# owl-digital.net
KiCad netlist of a schematic drawn in EAGLE
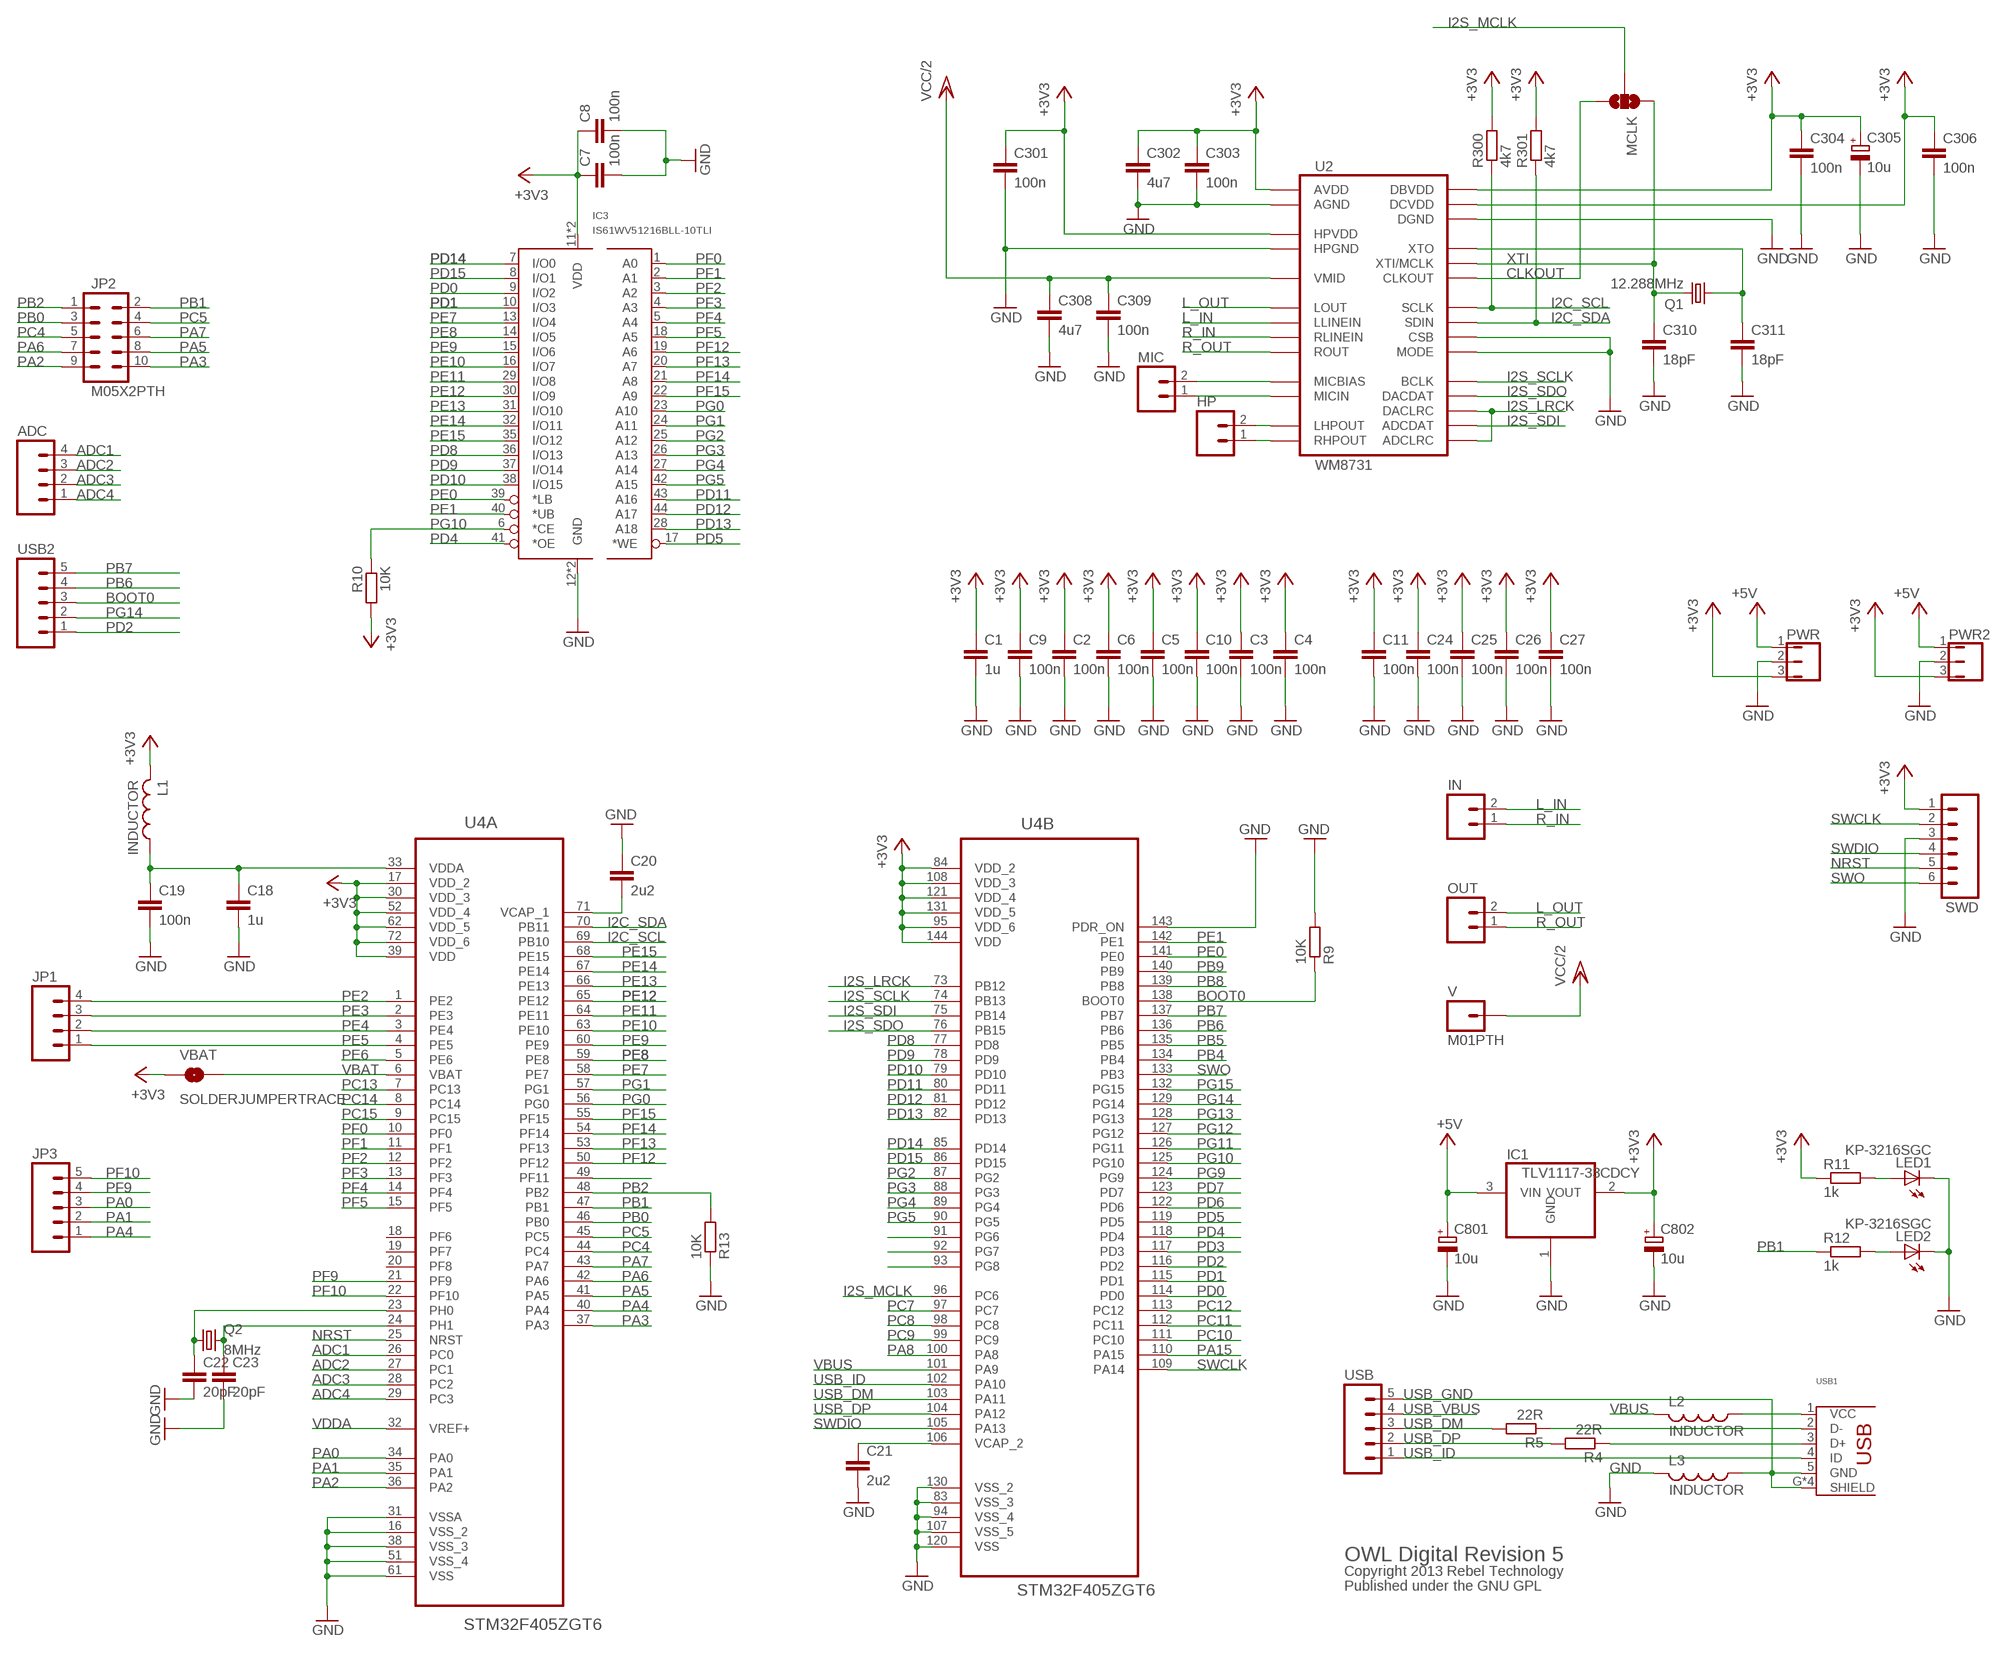
[diagram p0: schematic, sheet 1]

(export (version "E")
  (design (tool "Eeschema 10.0.6"))
  (components
    (comp (ref "ADC")
      (value "M04PTH")
      (footprint "eagle-import:1X04")
      (libsource (lib "eagle-import") (part "M04PTH"))
    )
    (comp (ref "C1")
      (value "1u")
      (footprint "eagle-import:C0603")
      (libsource (lib "eagle-import") (part "C-EUC0603"))
    )
    (comp (ref "C2")
      (value "100n")
      (footprint "eagle-import:C0603")
      (libsource (lib "eagle-import") (part "C-EUC0603"))
    )
    (comp (ref "C3")
      (value "100n")
      (footprint "eagle-import:C0603")
      (libsource (lib "eagle-import") (part "C-EUC0603"))
    )
    (comp (ref "C4")
      (value "100n")
      (footprint "eagle-import:C0603")
      (libsource (lib "eagle-import") (part "C-EUC0603"))
    )
    (comp (ref "C5")
      (value "100n")
      (footprint "eagle-import:C0603")
      (libsource (lib "eagle-import") (part "C-EUC0603"))
    )
    (comp (ref "C6")
      (value "100n")
      (footprint "eagle-import:C0603")
      (libsource (lib "eagle-import") (part "C-EUC0603"))
    )
    (comp (ref "C7")
      (value "100n")
      (footprint "eagle-import:C0603")
      (libsource (lib "eagle-import") (part "C-EUC0603"))
    )
    (comp (ref "C8")
      (value "100n")
      (footprint "eagle-import:C0603")
      (libsource (lib "eagle-import") (part "C-EUC0603"))
    )
    (comp (ref "C9")
      (value "100n")
      (footprint "eagle-import:C0603")
      (libsource (lib "eagle-import") (part "C-EUC0603"))
    )
    (comp (ref "C10")
      (value "100n")
      (footprint "eagle-import:C0603")
      (libsource (lib "eagle-import") (part "C-EUC0603"))
    )
    (comp (ref "C11")
      (value "100n")
      (footprint "eagle-import:C0603")
      (libsource (lib "eagle-import") (part "C-EUC0603"))
    )
    (comp (ref "C18")
      (value "1u")
      (footprint "eagle-import:C0603")
      (libsource (lib "eagle-import") (part "C-EUC0603"))
    )
    (comp (ref "C19")
      (value "100n")
      (footprint "eagle-import:C0603")
      (libsource (lib "eagle-import") (part "C-EUC0603"))
    )
    (comp (ref "C20")
      (value "2u2")
      (footprint "eagle-import:C0603")
      (libsource (lib "eagle-import") (part "C-EUC0603"))
    )
    (comp (ref "C21")
      (value "2u2")
      (footprint "eagle-import:C0603")
      (libsource (lib "eagle-import") (part "C-EUC0603"))
    )
    (comp (ref "C22")
      (value "20pF")
      (footprint "eagle-import:C0603")
      (libsource (lib "eagle-import") (part "C-EUC0603"))
    )
    (comp (ref "C23")
      (value "20pF")
      (footprint "eagle-import:C0603")
      (libsource (lib "eagle-import") (part "C-EUC0603"))
    )
    (comp (ref "C24")
      (value "100n")
      (footprint "eagle-import:C0603")
      (libsource (lib "eagle-import") (part "C-EUC0603"))
    )
    (comp (ref "C25")
      (value "100n")
      (footprint "eagle-import:C0603")
      (libsource (lib "eagle-import") (part "C-EUC0603"))
    )
    (comp (ref "C26")
      (value "100n")
      (footprint "eagle-import:C0603")
      (libsource (lib "eagle-import") (part "C-EUC0603"))
    )
    (comp (ref "C27")
      (value "100n")
      (footprint "eagle-import:C0603")
      (libsource (lib "eagle-import") (part "C-EUC0603"))
    )
    (comp (ref "C301")
      (value "100n")
      (footprint "eagle-import:C0603")
      (libsource (lib "eagle-import") (part "C-EUC0603"))
    )
    (comp (ref "C302")
      (value "4u7")
      (footprint "eagle-import:C1206")
      (libsource (lib "eagle-import") (part "C-EUC1206"))
    )
    (comp (ref "C303")
      (value "100n")
      (footprint "eagle-import:C0603")
      (libsource (lib "eagle-import") (part "C-EUC0603"))
    )
    (comp (ref "C304")
      (value "100n")
      (footprint "eagle-import:C0603")
      (libsource (lib "eagle-import") (part "C-EUC0603"))
    )
    (comp (ref "C305")
      (value "10u")
      (footprint "eagle-import:PANASONIC_A")
      (libsource (lib "eagle-import") (part "CPOL-EUA"))
    )
    (comp (ref "C306")
      (value "100n")
      (footprint "eagle-import:C0603")
      (libsource (lib "eagle-import") (part "C-EUC0603"))
    )
    (comp (ref "C308")
      (value "4u7")
      (footprint "eagle-import:C1206")
      (libsource (lib "eagle-import") (part "C-EUC1206"))
    )
    (comp (ref "C309")
      (value "100n")
      (footprint "eagle-import:C0603")
      (libsource (lib "eagle-import") (part "C-EUC0603"))
    )
    (comp (ref "C310")
      (value "18pF")
      (footprint "eagle-import:C0603")
      (libsource (lib "eagle-import") (part "C-EUC0603"))
    )
    (comp (ref "C311")
      (value "18pF")
      (footprint "eagle-import:C0603")
      (libsource (lib "eagle-import") (part "C-EUC0603"))
    )
    (comp (ref "C801")
      (value "10u")
      (footprint "eagle-import:PANASONIC_A")
      (libsource (lib "eagle-import") (part "CPOL-EUA"))
    )
    (comp (ref "C802")
      (value "10u")
      (footprint "eagle-import:PANASONIC_A")
      (libsource (lib "eagle-import") (part "CPOL-EUA"))
    )
    (comp (ref "HP")
      (value "M02PTH")
      (footprint "eagle-import:1X02")
      (libsource (lib "eagle-import") (part "M02PTH"))
    )
    (comp (ref "IC1")
      (value "TLV1117-33CDCY")
      (footprint "eagle-import:SOT223")
      (fields (field (name "MPN") "REG1117"))
      (libsource (lib "eagle-import") (part "REG1117"))
    )
    (comp (ref "IC3")
      (value "IS61WV51216BLL-10TLI")
      (footprint "eagle-import:TSOP44-II")
      (libsource (lib "eagle-import") (part "IS61WV51216BLL-10TLI"))
    )
    (comp (ref "IN")
      (value "M02PTH")
      (footprint "eagle-import:1X02")
      (libsource (lib "eagle-import") (part "M02PTH"))
    )
    (comp (ref "JP1")
      (value "M04PTH")
      (footprint "eagle-import:1X04")
      (libsource (lib "eagle-import") (part "M04PTH"))
    )
    (comp (ref "JP2")
      (value "M05X2PTH")
      (footprint "eagle-import:AVR_ICSP")
      (libsource (lib "eagle-import") (part "M05X2PTH"))
    )
    (comp (ref "JP3")
      (value "M05PTH")
      (footprint "eagle-import:1X05")
      (libsource (lib "eagle-import") (part "M05PTH"))
    )
    (comp (ref "L1")
      (value "INDUCTOR")
      (footprint "eagle-import:0603")
      (libsource (lib "eagle-import") (part "INDUCTOR"))
    )
    (comp (ref "L2")
      (value "INDUCTOR")
      (footprint "eagle-import:0603")
      (libsource (lib "eagle-import") (part "INDUCTOR"))
    )
    (comp (ref "L3")
      (value "INDUCTOR")
      (footprint "eagle-import:0603")
      (libsource (lib "eagle-import") (part "INDUCTOR"))
    )
    (comp (ref "LED1")
      (value "KP-3216SGC")
      (footprint "eagle-import:LED-1206")
      (libsource (lib "eagle-import") (part "LED1206"))
    )
    (comp (ref "LED2")
      (value "KP-3216SGC")
      (footprint "eagle-import:LED-1206")
      (libsource (lib "eagle-import") (part "LED1206"))
    )
    (comp (ref "MCLK")
      (value "SOLDERJUMPER_2WAY")
      (footprint "eagle-import:SJ_3_SML")
      (libsource (lib "eagle-import") (part "SOLDERJUMPER_2WAY"))
    )
    (comp (ref "MIC")
      (value "M02PTH")
      (footprint "eagle-import:1X02")
      (libsource (lib "eagle-import") (part "M02PTH"))
    )
    (comp (ref "OUT")
      (value "M02PTH")
      (footprint "eagle-import:1X02")
      (libsource (lib "eagle-import") (part "M02PTH"))
    )
    (comp (ref "PWR")
      (value "JMP/3P/SIP")
      (footprint "eagle-import:JMP_3P_SIP")
      (libsource (lib "eagle-import") (part "JMP/3P/SIP"))
    )
    (comp (ref "PWR2")
      (value "JMP/3P/SIP")
      (footprint "eagle-import:JMP_3P_SIP")
      (libsource (lib "eagle-import") (part "JMP/3P/SIP"))
    )
    (comp (ref "Q1")
      (value "12.288MHz")
      (footprint "eagle-import:HC49UP")
      (libsource (lib "eagle-import") (part "CRYSTALHC49UP"))
    )
    (comp (ref "Q2")
      (value "8MHz")
      (footprint "eagle-import:HC49UP")
      (libsource (lib "eagle-import") (part "CRYSTALHC49UP"))
    )
    (comp (ref "R4")
      (value "22R")
      (footprint "eagle-import:0603")
      (libsource (lib "eagle-import") (part "R-EU_0603"))
    )
    (comp (ref "R5")
      (value "22R")
      (footprint "eagle-import:0603")
      (libsource (lib "eagle-import") (part "R-EU_0603"))
    )
    (comp (ref "R9")
      (value "10K")
      (footprint "eagle-import:0603")
      (libsource (lib "eagle-import") (part "R-EU_0603"))
    )
    (comp (ref "R10")
      (value "10K")
      (footprint "eagle-import:0603")
      (libsource (lib "eagle-import") (part "R-EU_0603"))
    )
    (comp (ref "R11")
      (value "1k")
      (footprint "eagle-import:0603")
      (libsource (lib "eagle-import") (part "R-EU_0603"))
    )
    (comp (ref "R12")
      (value "1k")
      (footprint "eagle-import:0603")
      (libsource (lib "eagle-import") (part "R-EU_0603"))
    )
    (comp (ref "R13")
      (value "10K")
      (footprint "eagle-import:0603")
      (libsource (lib "eagle-import") (part "R-EU_0603"))
    )
    (comp (ref "R300")
      (value "4k7")
      (footprint "eagle-import:0603")
      (libsource (lib "eagle-import") (part "R-EU_0603"))
    )
    (comp (ref "R301")
      (value "4k7")
      (footprint "eagle-import:0603")
      (libsource (lib "eagle-import") (part "R-EU_0603"))
    )
    (comp (ref "SWD")
      (value "M06SIP")
      (footprint "eagle-import:1X06")
      (libsource (lib "eagle-import") (part "M06SIP"))
    )
    (comp (ref "U2")
      (value "WM8731")
      (footprint "eagle-import:28-SSOP")
      (libsource (lib "eagle-import") (part "WM8731"))
    )
    (comp (ref "U4")
      (value "STM32F405ZGT6")
      (footprint "eagle-import:QFP50P2200X2200X160-144N")
      (fields (field (name "FARNELL") "221-5225"))
      (libsource (lib "eagle-import") (part "STM32F405ZGT6"))
    )
    (comp (ref "USB")
      (value "M05PTH")
      (footprint "eagle-import:1X05")
      (libsource (lib "eagle-import") (part "M05PTH"))
    )
    (comp (ref "USB1")
      (value "USB_HRS_ZX62-B-5PA(11)MICRO.B")
      (footprint "eagle-import:HRS_ZX62RD-AB-5P8")
      (libsource (lib "eagle-import") (part "USB_HRS_ZX62-B-5PA(11)MICRO.B"))
    )
    (comp (ref "USB2")
      (value "M05PTH")
      (footprint "eagle-import:1X05")
      (libsource (lib "eagle-import") (part "M05PTH"))
    )
    (comp (ref "V")
      (value "M01PTH")
      (footprint "eagle-import:1X01")
      (libsource (lib "eagle-import") (part "M01PTH"))
    )
    (comp (ref "VBAT")
      (value "SOLDERJUMPERTRACE")
      (footprint "eagle-import:SJ_2S-TRACE")
      (libsource (lib "eagle-import") (part "SOLDERJUMPERTRACE"))
    )
  )
  (nets
    (net (code "1") (name "+3V3") (class "Default")
      (node (ref "C1") (pin "1") (pinfunction "1_1") (pintype "passive"))
      (node (ref "C10") (pin "1") (pinfunction "1_1") (pintype "passive"))
      (node (ref "C11") (pin "1") (pinfunction "1_1") (pintype "passive"))
      (node (ref "C2") (pin "1") (pinfunction "1_1") (pintype "passive"))
      (node (ref "C24") (pin "1") (pinfunction "1_1") (pintype "passive"))
      (node (ref "C25") (pin "1") (pinfunction "1_1") (pintype "passive"))
      (node (ref "C26") (pin "1") (pinfunction "1_1") (pintype "passive"))
      (node (ref "C27") (pin "1") (pinfunction "1_1") (pintype "passive"))
      (node (ref "C3") (pin "1") (pinfunction "1_1") (pintype "passive"))
      (node (ref "C301") (pin "1") (pinfunction "1_1") (pintype "passive"))
      (node (ref "C302") (pin "1") (pinfunction "1_1") (pintype "passive"))
      (node (ref "C303") (pin "1") (pinfunction "1_1") (pintype "passive"))
      (node (ref "C304") (pin "1") (pinfunction "1_1") (pintype "passive"))
      (node (ref "C305") (pin "+") (pinfunction "+_+") (pintype "passive"))
      (node (ref "C306") (pin "1") (pinfunction "1_1") (pintype "passive"))
      (node (ref "C4") (pin "1") (pinfunction "1_1") (pintype "passive"))
      (node (ref "C5") (pin "1") (pinfunction "1_1") (pintype "passive"))
      (node (ref "C6") (pin "1") (pinfunction "1_1") (pintype "passive"))
      (node (ref "C7") (pin "1") (pinfunction "1_1") (pintype "passive"))
      (node (ref "C8") (pin "1") (pinfunction "1_1") (pintype "passive"))
      (node (ref "C802") (pin "+") (pinfunction "+_+") (pintype "passive"))
      (node (ref "C9") (pin "1") (pinfunction "1_1") (pintype "passive"))
      (node (ref "IC1") (pin "2") (pinfunction "VOUT_2") (pintype "output"))
      (node (ref "IC3") (pin "11") (pinfunction "VDD_11") (pintype "power_in"))
      (node (ref "IC3") (pin "33") (pinfunction "VDD_33") (pintype "power_in"))
      (node (ref "L1") (pin "2") (pinfunction "2_2") (pintype "passive"))
      (node (ref "PWR") (pin "3") (pinfunction "3_3") (pintype "passive"))
      (node (ref "PWR2") (pin "3") (pinfunction "3_3") (pintype "passive"))
      (node (ref "R10") (pin "2") (pinfunction "2_2") (pintype "passive"))
      (node (ref "R11") (pin "1") (pinfunction "1_1") (pintype "passive"))
      (node (ref "R300") (pin "2") (pinfunction "2_2") (pintype "passive"))
      (node (ref "R301") (pin "2") (pinfunction "2_2") (pintype "passive"))
      (node (ref "SWD") (pin "1") (pinfunction "1_1") (pintype "passive"))
      (node (ref "U2") (pin "P$1") (pinfunction "DBVDD_P$1") (pintype "power_in"))
      (node (ref "U2") (pin "P$14") (pinfunction "AVDD_P$14") (pintype "power_in"))
      (node (ref "U2") (pin "P$27") (pinfunction "DCVDD_P$27") (pintype "power_in"))
      (node (ref "U2") (pin "P$8") (pinfunction "HPVDD_P$8") (pintype "power_in"))
      (node (ref "U4") (pin "108") (pinfunction "VDD_3_108") (pintype "power_in"))
      (node (ref "U4") (pin "121") (pinfunction "VDD_4_121") (pintype "power_in"))
      (node (ref "U4") (pin "131") (pinfunction "VDD_5_131") (pintype "power_in"))
      (node (ref "U4") (pin "144") (pinfunction "VDD_144") (pintype "power_in"))
      (node (ref "U4") (pin "17") (pinfunction "VDD_2_17") (pintype "power_in"))
      (node (ref "U4") (pin "30") (pinfunction "VDD_3_30") (pintype "power_in"))
      (node (ref "U4") (pin "39") (pinfunction "VDD_39") (pintype "power_in"))
      (node (ref "U4") (pin "52") (pinfunction "VDD_4_52") (pintype "power_in"))
      (node (ref "U4") (pin "62") (pinfunction "VDD_5_62") (pintype "power_in"))
      (node (ref "U4") (pin "72") (pinfunction "VDD_6_72") (pintype "power_in"))
      (node (ref "U4") (pin "84") (pinfunction "VDD_2_84") (pintype "power_in"))
      (node (ref "U4") (pin "95") (pinfunction "VDD_6_95") (pintype "power_in"))
      (node (ref "VBAT") (pin "1") (pinfunction "1_1") (pintype "passive"))
    )
    (net (code "2") (name "+5V") (class "Default")
      (node (ref "C801") (pin "+") (pinfunction "+_+") (pintype "passive"))
      (node (ref "IC1") (pin "3") (pinfunction "VIN_3") (pintype "input"))
      (node (ref "PWR") (pin "1") (pinfunction "1_1") (pintype "passive"))
      (node (ref "PWR2") (pin "1") (pinfunction "1_1") (pintype "passive"))
    )
    (net (code "3") (name "/ADC1") (class "Default")
      (node (ref "ADC") (pin "4") (pinfunction "4_4") (pintype "passive"))
      (node (ref "U4") (pin "26") (pinfunction "PC0_26") (pintype "bidirectional"))
    )
    (net (code "4") (name "/ADC2") (class "Default")
      (node (ref "ADC") (pin "3") (pinfunction "3_3") (pintype "passive"))
      (node (ref "U4") (pin "27") (pinfunction "PC1_27") (pintype "bidirectional"))
    )
    (net (code "5") (name "/ADC3") (class "Default")
      (node (ref "ADC") (pin "2") (pinfunction "2_2") (pintype "passive"))
      (node (ref "U4") (pin "28") (pinfunction "PC2_28") (pintype "bidirectional"))
    )
    (net (code "6") (name "/ADC4") (class "Default")
      (node (ref "ADC") (pin "1") (pinfunction "1_1") (pintype "passive"))
      (node (ref "U4") (pin "29") (pinfunction "PC3_29") (pintype "bidirectional"))
    )
    (net (code "7") (name "/BOOT0") (class "Default")
      (node (ref "R9") (pin "1") (pinfunction "1_1") (pintype "passive"))
      (node (ref "U4") (pin "138") (pinfunction "BOOT0_138") (pintype "passive"))
      (node (ref "USB2") (pin "3") (pinfunction "3_3") (pintype "passive"))
    )
    (net (code "8") (name "/CLKOUT") (class "Default")
      (node (ref "MCLK") (pin "3") (pinfunction "3_3") (pintype "passive"))
      (node (ref "U2") (pin "P$2") (pinfunction "CLKOUT_P$2") (pintype "output"))
    )
    (net (code "9") (name "/I2C_SCL") (class "Default")
      (node (ref "R300") (pin "1") (pinfunction "1_1") (pintype "passive"))
      (node (ref "U2") (pin "P$24") (pinfunction "SCLK_P$24") (pintype "input"))
      (node (ref "U4") (pin "69") (pinfunction "PB10_69") (pintype "bidirectional"))
    )
    (net (code "10") (name "/I2C_SDA") (class "Default")
      (node (ref "R301") (pin "1") (pinfunction "1_1") (pintype "passive"))
      (node (ref "U2") (pin "P$23") (pinfunction "SDIN_P$23") (pintype "bidirectional"))
      (node (ref "U4") (pin "70") (pinfunction "PB11_70") (pintype "bidirectional"))
    )
    (net (code "11") (name "/I2S_LRCK") (class "Default")
      (node (ref "U2") (pin "P$5") (pinfunction "DACLRC_P$5") (pintype "bidirectional"))
      (node (ref "U2") (pin "P$7") (pinfunction "ADCLRC_P$7") (pintype "bidirectional"))
      (node (ref "U4") (pin "73") (pinfunction "PB12_73") (pintype "bidirectional"))
    )
    (net (code "12") (name "/I2S_MCLK") (class "Default")
      (node (ref "MCLK") (pin "2") (pinfunction "2_2") (pintype "passive"))
      (node (ref "U4") (pin "96") (pinfunction "PC6_96") (pintype "bidirectional"))
    )
    (net (code "13") (name "/I2S_SCLK") (class "Default")
      (node (ref "U2") (pin "P$3") (pinfunction "BCLK_P$3") (pintype "bidirectional"))
      (node (ref "U4") (pin "74") (pinfunction "PB13_74") (pintype "bidirectional"))
    )
    (net (code "14") (name "/I2S_SDI") (class "Default")
      (node (ref "U2") (pin "P$6") (pinfunction "ADCDAT_P$6") (pintype "output"))
      (node (ref "U4") (pin "75") (pinfunction "PB14_75") (pintype "bidirectional"))
    )
    (net (code "15") (name "/I2S_SDO") (class "Default")
      (node (ref "U2") (pin "P$4") (pinfunction "DACDAT_P$4") (pintype "input"))
      (node (ref "U4") (pin "76") (pinfunction "PB15_76") (pintype "bidirectional"))
    )
    (net (code "16") (name "/L_IN") (class "Default")
      (node (ref "IN") (pin "2") (pinfunction "2_2") (pintype "passive"))
      (node (ref "U2") (pin "P$20") (pinfunction "LLINEIN_P$20") (pintype "input"))
    )
    (net (code "17") (name "/L_OUT") (class "Default")
      (node (ref "OUT") (pin "2") (pinfunction "2_2") (pintype "passive"))
      (node (ref "U2") (pin "P$12") (pinfunction "LOUT_P$12") (pintype "output"))
    )
    (net (code "18") (name "/NRST") (class "Default")
      (node (ref "SWD") (pin "5") (pinfunction "5_5") (pintype "passive"))
      (node (ref "U4") (pin "25") (pinfunction "NRST_25") (pintype "passive"))
    )
    (net (code "19") (name "/PA0") (class "Default")
      (node (ref "JP3") (pin "3") (pinfunction "3_3") (pintype "passive"))
      (node (ref "U4") (pin "34") (pinfunction "PA0_34") (pintype "bidirectional"))
    )
    (net (code "20") (name "/PA1") (class "Default")
      (node (ref "JP3") (pin "2") (pinfunction "2_2") (pintype "passive"))
      (node (ref "U4") (pin "35") (pinfunction "PA1_35") (pintype "bidirectional"))
    )
    (net (code "21") (name "/PA2") (class "Default")
      (node (ref "JP2") (pin "9") (pinfunction "9_9") (pintype "passive"))
      (node (ref "U4") (pin "36") (pinfunction "PA2_36") (pintype "bidirectional"))
    )
    (net (code "22") (name "/PA3") (class "Default")
      (node (ref "JP2") (pin "10") (pinfunction "10_10") (pintype "passive"))
      (node (ref "U4") (pin "37") (pinfunction "PA3_37") (pintype "bidirectional"))
    )
    (net (code "23") (name "/PA4") (class "Default")
      (node (ref "JP3") (pin "1") (pinfunction "1_1") (pintype "passive"))
      (node (ref "U4") (pin "40") (pinfunction "PA4_40") (pintype "bidirectional"))
    )
    (net (code "24") (name "/PA5") (class "Default")
      (node (ref "JP2") (pin "8") (pinfunction "8_8") (pintype "passive"))
      (node (ref "U4") (pin "41") (pinfunction "PA5_41") (pintype "bidirectional"))
    )
    (net (code "25") (name "/PA6") (class "Default")
      (node (ref "JP2") (pin "7") (pinfunction "7_7") (pintype "passive"))
      (node (ref "U4") (pin "42") (pinfunction "PA6_42") (pintype "bidirectional"))
    )
    (net (code "26") (name "/PA7") (class "Default")
      (node (ref "JP2") (pin "6") (pinfunction "6_6") (pintype "passive"))
      (node (ref "U4") (pin "43") (pinfunction "PA7_43") (pintype "bidirectional"))
    )
    (net (code "27") (name "/PA8") (class "Default")
      (node (ref "U4") (pin "100") (pinfunction "PA8_100") (pintype "bidirectional"))
    )
    (net (code "28") (name "/PA15") (class "Default")
      (node (ref "U4") (pin "110") (pinfunction "PA15_110") (pintype "bidirectional"))
    )
    (net (code "29") (name "/PB0") (class "Default")
      (node (ref "JP2") (pin "3") (pinfunction "3_3") (pintype "passive"))
      (node (ref "U4") (pin "46") (pinfunction "PB0_46") (pintype "bidirectional"))
    )
    (net (code "30") (name "/PB1") (class "Default")
      (node (ref "JP2") (pin "2") (pinfunction "2_2") (pintype "passive"))
      (node (ref "R12") (pin "1") (pinfunction "1_1") (pintype "passive"))
      (node (ref "U4") (pin "47") (pinfunction "PB1_47") (pintype "bidirectional"))
    )
    (net (code "31") (name "/PB2") (class "Default")
      (node (ref "JP2") (pin "1") (pinfunction "1_1") (pintype "passive"))
      (node (ref "R13") (pin "2") (pinfunction "2_2") (pintype "passive"))
      (node (ref "U4") (pin "48") (pinfunction "PB2_48") (pintype "bidirectional"))
    )
    (net (code "32") (name "/PB4") (class "Default")
      (node (ref "U4") (pin "134") (pinfunction "PB4_134") (pintype "bidirectional"))
    )
    (net (code "33") (name "/PB5") (class "Default")
      (node (ref "U4") (pin "135") (pinfunction "PB5_135") (pintype "bidirectional"))
    )
    (net (code "34") (name "/PB6") (class "Default")
      (node (ref "U4") (pin "136") (pinfunction "PB6_136") (pintype "bidirectional"))
      (node (ref "USB2") (pin "4") (pinfunction "4_4") (pintype "passive"))
    )
    (net (code "35") (name "/PB7") (class "Default")
      (node (ref "U4") (pin "137") (pinfunction "PB7_137") (pintype "bidirectional"))
      (node (ref "USB2") (pin "5") (pinfunction "5_5") (pintype "passive"))
    )
    (net (code "36") (name "/PB8") (class "Default")
      (node (ref "U4") (pin "139") (pinfunction "PB8_139") (pintype "bidirectional"))
    )
    (net (code "37") (name "/PB9") (class "Default")
      (node (ref "U4") (pin "140") (pinfunction "PB9_140") (pintype "bidirectional"))
    )
    (net (code "38") (name "/PC4") (class "Default")
      (node (ref "JP2") (pin "5") (pinfunction "5_5") (pintype "passive"))
      (node (ref "U4") (pin "44") (pinfunction "PC4_44") (pintype "bidirectional"))
    )
    (net (code "39") (name "/PC5") (class "Default")
      (node (ref "JP2") (pin "4") (pinfunction "4_4") (pintype "passive"))
      (node (ref "U4") (pin "45") (pinfunction "PC5_45") (pintype "bidirectional"))
    )
    (net (code "40") (name "/PC7") (class "Default")
      (node (ref "U4") (pin "97") (pinfunction "PC7_97") (pintype "bidirectional"))
    )
    (net (code "41") (name "/PC8") (class "Default")
      (node (ref "U4") (pin "98") (pinfunction "PC8_98") (pintype "bidirectional"))
    )
    (net (code "42") (name "/PC9") (class "Default")
      (node (ref "U4") (pin "99") (pinfunction "PC9_99") (pintype "bidirectional"))
    )
    (net (code "43") (name "/PC10") (class "Default")
      (node (ref "U4") (pin "111") (pinfunction "PC10_111") (pintype "bidirectional"))
    )
    (net (code "44") (name "/PC11") (class "Default")
      (node (ref "U4") (pin "112") (pinfunction "PC11_112") (pintype "bidirectional"))
    )
    (net (code "45") (name "/PC12") (class "Default")
      (node (ref "U4") (pin "113") (pinfunction "PC12_113") (pintype "bidirectional"))
    )
    (net (code "46") (name "/PC13") (class "Default")
      (node (ref "U4") (pin "7") (pinfunction "PC13_7") (pintype "bidirectional"))
    )
    (net (code "47") (name "/PC14") (class "Default")
      (node (ref "U4") (pin "8") (pinfunction "PC14_8") (pintype "bidirectional"))
    )
    (net (code "48") (name "/PC15") (class "Default")
      (node (ref "U4") (pin "9") (pinfunction "PC15_9") (pintype "bidirectional"))
    )
    (net (code "49") (name "/PD0") (class "Default")
      (node (ref "IC3") (pin "9") (pinfunction "I/O2_9") (pintype "bidirectional"))
      (node (ref "U4") (pin "114") (pinfunction "PD0_114") (pintype "bidirectional"))
    )
    (net (code "50") (name "/PD1") (class "Default")
      (node (ref "IC3") (pin "10") (pinfunction "I/O3_10") (pintype "bidirectional"))
      (node (ref "U4") (pin "115") (pinfunction "PD1_115") (pintype "bidirectional"))
    )
    (net (code "51") (name "/PD2") (class "Default")
      (node (ref "U4") (pin "116") (pinfunction "PD2_116") (pintype "bidirectional"))
      (node (ref "USB2") (pin "1") (pinfunction "1_1") (pintype "passive"))
    )
    (net (code "52") (name "/PD3") (class "Default")
      (node (ref "U4") (pin "117") (pinfunction "PD3_117") (pintype "bidirectional"))
    )
    (net (code "53") (name "/PD4") (class "Default")
      (node (ref "IC3") (pin "41") (pinfunction "*OE_41") (pintype "bidirectional"))
      (node (ref "U4") (pin "118") (pinfunction "PD4_118") (pintype "bidirectional"))
    )
    (net (code "54") (name "/PD5") (class "Default")
      (node (ref "IC3") (pin "17") (pinfunction "*WE_17") (pintype "bidirectional"))
      (node (ref "U4") (pin "119") (pinfunction "PD5_119") (pintype "bidirectional"))
    )
    (net (code "55") (name "/PD6") (class "Default")
      (node (ref "U4") (pin "122") (pinfunction "PD6_122") (pintype "bidirectional"))
    )
    (net (code "56") (name "/PD7") (class "Default")
      (node (ref "U4") (pin "123") (pinfunction "PD7_123") (pintype "bidirectional"))
    )
    (net (code "57") (name "/PD8") (class "Default")
      (node (ref "IC3") (pin "36") (pinfunction "I/O13_36") (pintype "bidirectional"))
      (node (ref "U4") (pin "77") (pinfunction "PD8_77") (pintype "bidirectional"))
    )
    (net (code "58") (name "/PD9") (class "Default")
      (node (ref "IC3") (pin "37") (pinfunction "I/O14_37") (pintype "bidirectional"))
      (node (ref "U4") (pin "78") (pinfunction "PD9_78") (pintype "bidirectional"))
    )
    (net (code "59") (name "/PD10") (class "Default")
      (node (ref "IC3") (pin "38") (pinfunction "I/O15_38") (pintype "bidirectional"))
      (node (ref "U4") (pin "79") (pinfunction "PD10_79") (pintype "bidirectional"))
    )
    (net (code "60") (name "/PD11") (class "Default")
      (node (ref "IC3") (pin "43") (pinfunction "A16_43") (pintype "input"))
      (node (ref "U4") (pin "80") (pinfunction "PD11_80") (pintype "bidirectional"))
    )
    (net (code "61") (name "/PD12") (class "Default")
      (node (ref "IC3") (pin "44") (pinfunction "A17_44") (pintype "input"))
      (node (ref "U4") (pin "81") (pinfunction "PD12_81") (pintype "bidirectional"))
    )
    (net (code "62") (name "/PD13") (class "Default")
      (node (ref "IC3") (pin "28") (pinfunction "A18_28") (pintype "input"))
      (node (ref "U4") (pin "82") (pinfunction "PD13_82") (pintype "bidirectional"))
    )
    (net (code "63") (name "/PD14") (class "Default")
      (node (ref "IC3") (pin "7") (pinfunction "I/O0_7") (pintype "bidirectional"))
      (node (ref "U4") (pin "85") (pinfunction "PD14_85") (pintype "bidirectional"))
    )
    (net (code "64") (name "/PD15") (class "Default")
      (node (ref "IC3") (pin "8") (pinfunction "I/O1_8") (pintype "bidirectional"))
      (node (ref "U4") (pin "86") (pinfunction "PD15_86") (pintype "bidirectional"))
    )
    (net (code "65") (name "/PE0") (class "Default")
      (node (ref "IC3") (pin "39") (pinfunction "*LB_39") (pintype "bidirectional"))
      (node (ref "U4") (pin "141") (pinfunction "PE0_141") (pintype "bidirectional"))
    )
    (net (code "66") (name "/PE1") (class "Default")
      (node (ref "IC3") (pin "40") (pinfunction "*UB_40") (pintype "bidirectional"))
      (node (ref "U4") (pin "142") (pinfunction "PE1_142") (pintype "bidirectional"))
    )
    (net (code "67") (name "/PE2") (class "Default")
      (node (ref "JP1") (pin "4") (pinfunction "4_4") (pintype "passive"))
      (node (ref "U4") (pin "1") (pinfunction "PE2_1") (pintype "bidirectional"))
    )
    (net (code "68") (name "/PE3") (class "Default")
      (node (ref "JP1") (pin "3") (pinfunction "3_3") (pintype "passive"))
      (node (ref "U4") (pin "2") (pinfunction "PE3_2") (pintype "bidirectional"))
    )
    (net (code "69") (name "/PE4") (class "Default")
      (node (ref "JP1") (pin "2") (pinfunction "2_2") (pintype "passive"))
      (node (ref "U4") (pin "3") (pinfunction "PE4_3") (pintype "bidirectional"))
    )
    (net (code "70") (name "/PE5") (class "Default")
      (node (ref "JP1") (pin "1") (pinfunction "1_1") (pintype "passive"))
      (node (ref "U4") (pin "4") (pinfunction "PE5_4") (pintype "bidirectional"))
    )
    (net (code "71") (name "/PE6") (class "Default")
      (node (ref "U4") (pin "5") (pinfunction "PE6_5") (pintype "bidirectional"))
    )
    (net (code "72") (name "/PE7") (class "Default")
      (node (ref "IC3") (pin "13") (pinfunction "I/O4_13") (pintype "bidirectional"))
      (node (ref "U4") (pin "58") (pinfunction "PE7_58") (pintype "bidirectional"))
    )
    (net (code "73") (name "/PE8") (class "Default")
      (node (ref "IC3") (pin "14") (pinfunction "I/O5_14") (pintype "bidirectional"))
      (node (ref "U4") (pin "59") (pinfunction "PE8_59") (pintype "bidirectional"))
    )
    (net (code "74") (name "/PE9") (class "Default")
      (node (ref "IC3") (pin "15") (pinfunction "I/O6_15") (pintype "bidirectional"))
      (node (ref "U4") (pin "60") (pinfunction "PE9_60") (pintype "bidirectional"))
    )
    (net (code "75") (name "/PE10") (class "Default")
      (node (ref "IC3") (pin "16") (pinfunction "I/O7_16") (pintype "bidirectional"))
      (node (ref "U4") (pin "63") (pinfunction "PE10_63") (pintype "bidirectional"))
    )
    (net (code "76") (name "/PE11") (class "Default")
      (node (ref "IC3") (pin "29") (pinfunction "I/O8_29") (pintype "bidirectional"))
      (node (ref "U4") (pin "64") (pinfunction "PE11_64") (pintype "bidirectional"))
    )
    (net (code "77") (name "/PE12") (class "Default")
      (node (ref "IC3") (pin "30") (pinfunction "I/O9_30") (pintype "bidirectional"))
      (node (ref "U4") (pin "65") (pinfunction "PE12_65") (pintype "bidirectional"))
    )
    (net (code "78") (name "/PE13") (class "Default")
      (node (ref "IC3") (pin "31") (pinfunction "I/O10_31") (pintype "bidirectional"))
      (node (ref "U4") (pin "66") (pinfunction "PE13_66") (pintype "bidirectional"))
    )
    (net (code "79") (name "/PE14") (class "Default")
      (node (ref "IC3") (pin "32") (pinfunction "I/O11_32") (pintype "bidirectional"))
      (node (ref "U4") (pin "67") (pinfunction "PE14_67") (pintype "bidirectional"))
    )
    (net (code "80") (name "/PE15") (class "Default")
      (node (ref "IC3") (pin "35") (pinfunction "I/O12_35") (pintype "bidirectional"))
      (node (ref "U4") (pin "68") (pinfunction "PE15_68") (pintype "bidirectional"))
    )
    (net (code "81") (name "/PF0") (class "Default")
      (node (ref "IC3") (pin "1") (pinfunction "A0_1") (pintype "input"))
      (node (ref "U4") (pin "10") (pinfunction "PF0_10") (pintype "bidirectional"))
    )
    (net (code "82") (name "/PF1") (class "Default")
      (node (ref "IC3") (pin "2") (pinfunction "A1_2") (pintype "input"))
      (node (ref "U4") (pin "11") (pinfunction "PF1_11") (pintype "bidirectional"))
    )
    (net (code "83") (name "/PF2") (class "Default")
      (node (ref "IC3") (pin "3") (pinfunction "A2_3") (pintype "input"))
      (node (ref "U4") (pin "12") (pinfunction "PF2_12") (pintype "bidirectional"))
    )
    (net (code "84") (name "/PF3") (class "Default")
      (node (ref "IC3") (pin "4") (pinfunction "A3_4") (pintype "input"))
      (node (ref "U4") (pin "13") (pinfunction "PF3_13") (pintype "bidirectional"))
    )
    (net (code "85") (name "/PF4") (class "Default")
      (node (ref "IC3") (pin "5") (pinfunction "A4_5") (pintype "input"))
      (node (ref "U4") (pin "14") (pinfunction "PF4_14") (pintype "bidirectional"))
    )
    (net (code "86") (name "/PF5") (class "Default")
      (node (ref "IC3") (pin "18") (pinfunction "A5_18") (pintype "input"))
      (node (ref "U4") (pin "15") (pinfunction "PF5_15") (pintype "bidirectional"))
    )
    (net (code "87") (name "/PF9") (class "Default")
      (node (ref "JP3") (pin "4") (pinfunction "4_4") (pintype "passive"))
      (node (ref "U4") (pin "21") (pinfunction "PF9_21") (pintype "bidirectional"))
    )
    (net (code "88") (name "/PF10") (class "Default")
      (node (ref "JP3") (pin "5") (pinfunction "5_5") (pintype "passive"))
      (node (ref "U4") (pin "22") (pinfunction "PF10_22") (pintype "bidirectional"))
    )
    (net (code "89") (name "/PF12") (class "Default")
      (node (ref "IC3") (pin "19") (pinfunction "A6_19") (pintype "input"))
      (node (ref "U4") (pin "50") (pinfunction "PF12_50") (pintype "bidirectional"))
    )
    (net (code "90") (name "/PF13") (class "Default")
      (node (ref "IC3") (pin "20") (pinfunction "A7_20") (pintype "input"))
      (node (ref "U4") (pin "53") (pinfunction "PF13_53") (pintype "bidirectional"))
    )
    (net (code "91") (name "/PF14") (class "Default")
      (node (ref "IC3") (pin "21") (pinfunction "A8_21") (pintype "input"))
      (node (ref "U4") (pin "54") (pinfunction "PF14_54") (pintype "bidirectional"))
    )
    (net (code "92") (name "/PF15") (class "Default")
      (node (ref "IC3") (pin "22") (pinfunction "A9_22") (pintype "input"))
      (node (ref "U4") (pin "55") (pinfunction "PF15_55") (pintype "bidirectional"))
    )
    (net (code "93") (name "/PG0") (class "Default")
      (node (ref "IC3") (pin "23") (pinfunction "A10_23") (pintype "input"))
      (node (ref "U4") (pin "56") (pinfunction "PG0_56") (pintype "bidirectional"))
    )
    (net (code "94") (name "/PG1") (class "Default")
      (node (ref "IC3") (pin "24") (pinfunction "A11_24") (pintype "input"))
      (node (ref "U4") (pin "57") (pinfunction "PG1_57") (pintype "bidirectional"))
    )
    (net (code "95") (name "/PG2") (class "Default")
      (node (ref "IC3") (pin "25") (pinfunction "A12_25") (pintype "input"))
      (node (ref "U4") (pin "87") (pinfunction "PG2_87") (pintype "bidirectional"))
    )
    (net (code "96") (name "/PG3") (class "Default")
      (node (ref "IC3") (pin "26") (pinfunction "A13_26") (pintype "input"))
      (node (ref "U4") (pin "88") (pinfunction "PG3_88") (pintype "bidirectional"))
    )
    (net (code "97") (name "/PG4") (class "Default")
      (node (ref "IC3") (pin "27") (pinfunction "A14_27") (pintype "input"))
      (node (ref "U4") (pin "89") (pinfunction "PG4_89") (pintype "bidirectional"))
    )
    (net (code "98") (name "/PG5") (class "Default")
      (node (ref "IC3") (pin "42") (pinfunction "A15_42") (pintype "input"))
      (node (ref "U4") (pin "90") (pinfunction "PG5_90") (pintype "bidirectional"))
    )
    (net (code "99") (name "/PG9") (class "Default")
      (node (ref "U4") (pin "124") (pinfunction "PG9_124") (pintype "bidirectional"))
    )
    (net (code "100") (name "/PG10") (class "Default")
      (node (ref "IC3") (pin "6") (pinfunction "*CE_6") (pintype "bidirectional"))
      (node (ref "R10") (pin "1") (pinfunction "1_1") (pintype "passive"))
      (node (ref "U4") (pin "125") (pinfunction "PG10_125") (pintype "bidirectional"))
    )
    (net (code "101") (name "/PG11") (class "Default")
      (node (ref "U4") (pin "126") (pinfunction "PG11_126") (pintype "bidirectional"))
    )
    (net (code "102") (name "/PG12") (class "Default")
      (node (ref "U4") (pin "127") (pinfunction "PG12_127") (pintype "bidirectional"))
    )
    (net (code "103") (name "/PG13") (class "Default")
      (node (ref "U4") (pin "128") (pinfunction "PG13_128") (pintype "bidirectional"))
    )
    (net (code "104") (name "/PG14") (class "Default")
      (node (ref "U4") (pin "129") (pinfunction "PG14_129") (pintype "bidirectional"))
      (node (ref "USB2") (pin "2") (pinfunction "2_2") (pintype "passive"))
    )
    (net (code "105") (name "/PG15") (class "Default")
      (node (ref "U4") (pin "132") (pinfunction "PG15_132") (pintype "bidirectional"))
    )
    (net (code "106") (name "/R_IN") (class "Default")
      (node (ref "IN") (pin "1") (pinfunction "1_1") (pintype "passive"))
      (node (ref "U2") (pin "P$19") (pinfunction "RLINEIN_P$19") (pintype "input"))
    )
    (net (code "107") (name "/R_OUT") (class "Default")
      (node (ref "OUT") (pin "1") (pinfunction "1_1") (pintype "passive"))
      (node (ref "U2") (pin "P$13") (pinfunction "ROUT_P$13") (pintype "output"))
    )
    (net (code "108") (name "/SWCLK") (class "Default")
      (node (ref "SWD") (pin "2") (pinfunction "2_2") (pintype "passive"))
      (node (ref "U4") (pin "109") (pinfunction "PA14_109") (pintype "bidirectional"))
    )
    (net (code "109") (name "/SWDIO") (class "Default")
      (node (ref "SWD") (pin "4") (pinfunction "4_4") (pintype "passive"))
      (node (ref "U4") (pin "105") (pinfunction "PA13_105") (pintype "bidirectional"))
    )
    (net (code "110") (name "/SWO") (class "Default")
      (node (ref "SWD") (pin "6") (pinfunction "6_6") (pintype "passive"))
      (node (ref "U4") (pin "133") (pinfunction "PB3_133") (pintype "bidirectional"))
    )
    (net (code "111") (name "/USB_DM") (class "Default")
      (node (ref "R5") (pin "2") (pinfunction "2_2") (pintype "passive"))
      (node (ref "U4") (pin "103") (pinfunction "PA11_103") (pintype "bidirectional"))
      (node (ref "USB") (pin "3") (pinfunction "3_3") (pintype "passive"))
    )
    (net (code "112") (name "/USB_DP") (class "Default")
      (node (ref "R4") (pin "2") (pinfunction "2_2") (pintype "passive"))
      (node (ref "U4") (pin "104") (pinfunction "PA12_104") (pintype "bidirectional"))
      (node (ref "USB") (pin "2") (pinfunction "2_2") (pintype "passive"))
    )
    (net (code "113") (name "/USB_GND") (class "Default")
      (node (ref "L3") (pin "1") (pinfunction "1_1") (pintype "passive"))
      (node (ref "USB") (pin "5") (pinfunction "5_5") (pintype "passive"))
      (node (ref "USB1") (pin "5") (pinfunction "GND_5") (pintype "bidirectional"))
      (node (ref "USB1") (pin "G") (pinfunction "SHIELD_G") (pintype "bidirectional"))
      (node (ref "USB1") (pin "G2") (pinfunction "SHIELD_G2") (pintype "bidirectional"))
      (node (ref "USB1") (pin "G3") (pinfunction "SHIELD_G3") (pintype "bidirectional"))
      (node (ref "USB1") (pin "G4") (pinfunction "SHIELD_G4") (pintype "bidirectional"))
    )
    (net (code "114") (name "/USB_ID") (class "Default")
      (node (ref "U4") (pin "102") (pinfunction "PA10_102") (pintype "bidirectional"))
      (node (ref "USB") (pin "1") (pinfunction "1_1") (pintype "passive"))
      (node (ref "USB1") (pin "4") (pinfunction "ID_4") (pintype "bidirectional"))
    )
    (net (code "115") (name "/USB_VBUS") (class "Default")
      (node (ref "L2") (pin "1") (pinfunction "1_1") (pintype "passive"))
      (node (ref "USB") (pin "4") (pinfunction "4_4") (pintype "passive"))
      (node (ref "USB1") (pin "1") (pinfunction "VCC_1") (pintype "bidirectional"))
    )
    (net (code "116") (name "/VBAT") (class "Default")
      (node (ref "U4") (pin "6") (pinfunction "VBAT_6") (pintype "passive"))
      (node (ref "VBAT") (pin "2") (pinfunction "2_2") (pintype "passive"))
    )
    (net (code "117") (name "/VBUS") (class "Default")
      (node (ref "L2") (pin "2") (pinfunction "2_2") (pintype "passive"))
      (node (ref "U4") (pin "101") (pinfunction "PA9_101") (pintype "bidirectional"))
    )
    (net (code "118") (name "/VDDA") (class "Default")
      (node (ref "C18") (pin "1") (pinfunction "1_1") (pintype "passive"))
      (node (ref "C19") (pin "1") (pinfunction "1_1") (pintype "passive"))
      (node (ref "L1") (pin "1") (pinfunction "1_1") (pintype "passive"))
      (node (ref "U4") (pin "32") (pinfunction "VREF+_32") (pintype "passive"))
      (node (ref "U4") (pin "33") (pinfunction "VDDA_33") (pintype "power_in"))
    )
    (net (code "119") (name "/XTI") (class "Default")
      (node (ref "C310") (pin "1") (pinfunction "1_1") (pintype "passive"))
      (node (ref "MCLK") (pin "1") (pinfunction "1_1") (pintype "passive"))
      (node (ref "Q1") (pin "2") (pinfunction "2_2") (pintype "passive"))
      (node (ref "U2") (pin "P$25") (pinfunction "XTI/MCLK_P$25") (pintype "input"))
    )
    (net (code "120") (name "GND") (class "Default")
      (node (ref "C1") (pin "2") (pinfunction "2_2") (pintype "passive"))
      (node (ref "C10") (pin "2") (pinfunction "2_2") (pintype "passive"))
      (node (ref "C11") (pin "2") (pinfunction "2_2") (pintype "passive"))
      (node (ref "C18") (pin "2") (pinfunction "2_2") (pintype "passive"))
      (node (ref "C19") (pin "2") (pinfunction "2_2") (pintype "passive"))
      (node (ref "C2") (pin "2") (pinfunction "2_2") (pintype "passive"))
      (node (ref "C20") (pin "1") (pinfunction "1_1") (pintype "passive"))
      (node (ref "C21") (pin "2") (pinfunction "2_2") (pintype "passive"))
      (node (ref "C22") (pin "2") (pinfunction "2_2") (pintype "passive"))
      (node (ref "C23") (pin "2") (pinfunction "2_2") (pintype "passive"))
      (node (ref "C24") (pin "2") (pinfunction "2_2") (pintype "passive"))
      (node (ref "C25") (pin "2") (pinfunction "2_2") (pintype "passive"))
      (node (ref "C26") (pin "2") (pinfunction "2_2") (pintype "passive"))
      (node (ref "C27") (pin "2") (pinfunction "2_2") (pintype "passive"))
      (node (ref "C3") (pin "2") (pinfunction "2_2") (pintype "passive"))
      (node (ref "C301") (pin "2") (pinfunction "2_2") (pintype "passive"))
      (node (ref "C302") (pin "2") (pinfunction "2_2") (pintype "passive"))
      (node (ref "C303") (pin "2") (pinfunction "2_2") (pintype "passive"))
      (node (ref "C304") (pin "2") (pinfunction "2_2") (pintype "passive"))
      (node (ref "C305") (pin "-") (pinfunction "-_-") (pintype "passive"))
      (node (ref "C306") (pin "2") (pinfunction "2_2") (pintype "passive"))
      (node (ref "C308") (pin "2") (pinfunction "2_2") (pintype "passive"))
      (node (ref "C309") (pin "2") (pinfunction "2_2") (pintype "passive"))
      (node (ref "C310") (pin "2") (pinfunction "2_2") (pintype "passive"))
      (node (ref "C311") (pin "2") (pinfunction "2_2") (pintype "passive"))
      (node (ref "C4") (pin "2") (pinfunction "2_2") (pintype "passive"))
      (node (ref "C5") (pin "2") (pinfunction "2_2") (pintype "passive"))
      (node (ref "C6") (pin "2") (pinfunction "2_2") (pintype "passive"))
      (node (ref "C7") (pin "2") (pinfunction "2_2") (pintype "passive"))
      (node (ref "C8") (pin "2") (pinfunction "2_2") (pintype "passive"))
      (node (ref "C801") (pin "-") (pinfunction "-_-") (pintype "passive"))
      (node (ref "C802") (pin "-") (pinfunction "-_-") (pintype "passive"))
      (node (ref "C9") (pin "2") (pinfunction "2_2") (pintype "passive"))
      (node (ref "IC1") (pin "1") (pinfunction "GND_1") (pintype "power_in"))
      (node (ref "IC3") (pin "12") (pinfunction "GND_12") (pintype "power_in"))
      (node (ref "IC3") (pin "34") (pinfunction "GND_34") (pintype "power_in"))
      (node (ref "L3") (pin "2") (pinfunction "2_2") (pintype "passive"))
      (node (ref "LED1") (pin "C") (pinfunction "C_C") (pintype "passive"))
      (node (ref "LED2") (pin "C") (pinfunction "C_C") (pintype "passive"))
      (node (ref "PWR") (pin "2") (pinfunction "2_2") (pintype "passive"))
      (node (ref "PWR2") (pin "2") (pinfunction "2_2") (pintype "passive"))
      (node (ref "R13") (pin "1") (pinfunction "1_1") (pintype "passive"))
      (node (ref "R9") (pin "2") (pinfunction "2_2") (pintype "passive"))
      (node (ref "SWD") (pin "3") (pinfunction "3_3") (pintype "passive"))
      (node (ref "U2") (pin "P$11") (pinfunction "HPGND_P$11") (pintype "power_in"))
      (node (ref "U2") (pin "P$15") (pinfunction "AGND_P$15") (pintype "power_in"))
      (node (ref "U2") (pin "P$21") (pinfunction "MODE_P$21") (pintype "input"))
      (node (ref "U2") (pin "P$22") (pinfunction "CSB_P$22") (pintype "input"))
      (node (ref "U2") (pin "P$28") (pinfunction "DGND_P$28") (pintype "power_in"))
      (node (ref "U4") (pin "107") (pinfunction "VSS_5_107") (pintype "power_in"))
      (node (ref "U4") (pin "120") (pinfunction "VSS_120") (pintype "power_in"))
      (node (ref "U4") (pin "130") (pinfunction "VSS_2_130") (pintype "power_in"))
      (node (ref "U4") (pin "143") (pinfunction "PDR_ON_143") (pintype "passive"))
      (node (ref "U4") (pin "16") (pinfunction "VSS_2_16") (pintype "power_in"))
      (node (ref "U4") (pin "31") (pinfunction "VSSA_31") (pintype "power_in"))
      (node (ref "U4") (pin "38") (pinfunction "VSS_3_38") (pintype "power_in"))
      (node (ref "U4") (pin "51") (pinfunction "VSS_4_51") (pintype "power_in"))
      (node (ref "U4") (pin "61") (pinfunction "VSS_61") (pintype "power_in"))
      (node (ref "U4") (pin "83") (pinfunction "VSS_3_83") (pintype "power_in"))
      (node (ref "U4") (pin "94") (pinfunction "VSS_4_94") (pintype "power_in"))
    )
    (net (code "121") (name "Net-(LED1-PadA)") (class "Default")
      (node (ref "LED1") (pin "A") (pinfunction "A_A") (pintype "passive"))
      (node (ref "R11") (pin "2") (pinfunction "2_2") (pintype "passive"))
    )
    (net (code "122") (name "Net-(LED2-PadA)") (class "Default")
      (node (ref "LED2") (pin "A") (pinfunction "A_A") (pintype "passive"))
      (node (ref "R12") (pin "2") (pinfunction "2_2") (pintype "passive"))
    )
    (net (code "123") (name "Net-(U2-LHPOUT)") (class "Default")
      (node (ref "HP") (pin "2") (pinfunction "2_2") (pintype "passive"))
      (node (ref "U2") (pin "P$9") (pinfunction "LHPOUT_P$9") (pintype "output"))
    )
    (net (code "124") (name "Net-(U2-MICBIAS)") (class "Default")
      (node (ref "MIC") (pin "2") (pinfunction "2_2") (pintype "passive"))
      (node (ref "U2") (pin "P$17") (pinfunction "MICBIAS_P$17") (pintype "output"))
    )
    (net (code "125") (name "Net-(U2-MICIN)") (class "Default")
      (node (ref "MIC") (pin "1") (pinfunction "1_1") (pintype "passive"))
      (node (ref "U2") (pin "P$18") (pinfunction "MICIN_P$18") (pintype "input"))
    )
    (net (code "126") (name "Net-(U2-RHPOUT)") (class "Default")
      (node (ref "HP") (pin "1") (pinfunction "1_1") (pintype "passive"))
      (node (ref "U2") (pin "P$10") (pinfunction "RHPOUT_P$10") (pintype "output"))
    )
    (net (code "127") (name "Net-(U2-XTO)") (class "Default")
      (node (ref "C311") (pin "1") (pinfunction "1_1") (pintype "passive"))
      (node (ref "Q1") (pin "1") (pinfunction "1_1") (pintype "passive"))
      (node (ref "U2") (pin "P$26") (pinfunction "XTO_P$26") (pintype "output"))
    )
    (net (code "128") (name "Net-(U4A-PH0)") (class "Default")
      (node (ref "C22") (pin "1") (pinfunction "1_1") (pintype "passive"))
      (node (ref "Q2") (pin "1") (pinfunction "1_1") (pintype "passive"))
      (node (ref "U4") (pin "23") (pinfunction "PH0_23") (pintype "bidirectional"))
    )
    (net (code "129") (name "Net-(U4A-PH1)") (class "Default")
      (node (ref "C23") (pin "1") (pinfunction "1_1") (pintype "passive"))
      (node (ref "Q2") (pin "2") (pinfunction "2_2") (pintype "passive"))
      (node (ref "U4") (pin "24") (pinfunction "PH1_24") (pintype "bidirectional"))
    )
    (net (code "130") (name "Net-(U4A-VCAP_1)") (class "Default")
      (node (ref "C20") (pin "2") (pinfunction "2_2") (pintype "passive"))
      (node (ref "U4") (pin "71") (pinfunction "VCAP_1_71") (pintype "passive"))
    )
    (net (code "131") (name "Net-(U4B-VCAP_2)") (class "Default")
      (node (ref "C21") (pin "1") (pinfunction "1_1") (pintype "passive"))
      (node (ref "U4") (pin "106") (pinfunction "VCAP_2_106") (pintype "passive"))
    )
    (net (code "132") (name "Net-(USB1-D+)") (class "Default")
      (node (ref "R4") (pin "1") (pinfunction "1_1") (pintype "passive"))
      (node (ref "USB1") (pin "3") (pinfunction "D+_3") (pintype "bidirectional"))
    )
    (net (code "133") (name "Net-(USB1-D-)") (class "Default")
      (node (ref "R5") (pin "1") (pinfunction "1_1") (pintype "passive"))
      (node (ref "USB1") (pin "2") (pinfunction "D-_2") (pintype "bidirectional"))
    )
    (net (code "134") (name "VCC{slash}2") (class "Default")
      (node (ref "C308") (pin "1") (pinfunction "1_1") (pintype "passive"))
      (node (ref "C309") (pin "1") (pinfunction "1_1") (pintype "passive"))
      (node (ref "U2") (pin "P$16") (pinfunction "VMID_P$16") (pintype "output"))
      (node (ref "V") (pin "1") (pinfunction "1_1") (pintype "passive"))
    )
    (net (code "135") (name "unconnected-(U4A-PF6-Pad18)") (class "Default")
      (node (ref "U4") (pin "18") (pinfunction "PF6_18") (pintype "bidirectional"))
    )
    (net (code "136") (name "unconnected-(U4A-PF7-Pad19)") (class "Default")
      (node (ref "U4") (pin "19") (pinfunction "PF7_19") (pintype "bidirectional"))
    )
    (net (code "137") (name "unconnected-(U4A-PF8-Pad20)") (class "Default")
      (node (ref "U4") (pin "20") (pinfunction "PF8_20") (pintype "bidirectional"))
    )
    (net (code "138") (name "unconnected-(U4A-PF11-Pad49)") (class "Default")
      (node (ref "U4") (pin "49") (pinfunction "PF11_49") (pintype "bidirectional"))
    )
    (net (code "139") (name "unconnected-(U4B-PG6-Pad91)") (class "Default")
      (node (ref "U4") (pin "91") (pinfunction "PG6_91") (pintype "bidirectional"))
    )
    (net (code "140") (name "unconnected-(U4B-PG7-Pad92)") (class "Default")
      (node (ref "U4") (pin "92") (pinfunction "PG7_92") (pintype "bidirectional"))
    )
    (net (code "141") (name "unconnected-(U4B-PG8-Pad93)") (class "Default")
      (node (ref "U4") (pin "93") (pinfunction "PG8_93") (pintype "bidirectional"))
    )
  )
)
